# IR_Emitter.net
KiCad netlist of a schematic drawn in EAGLE
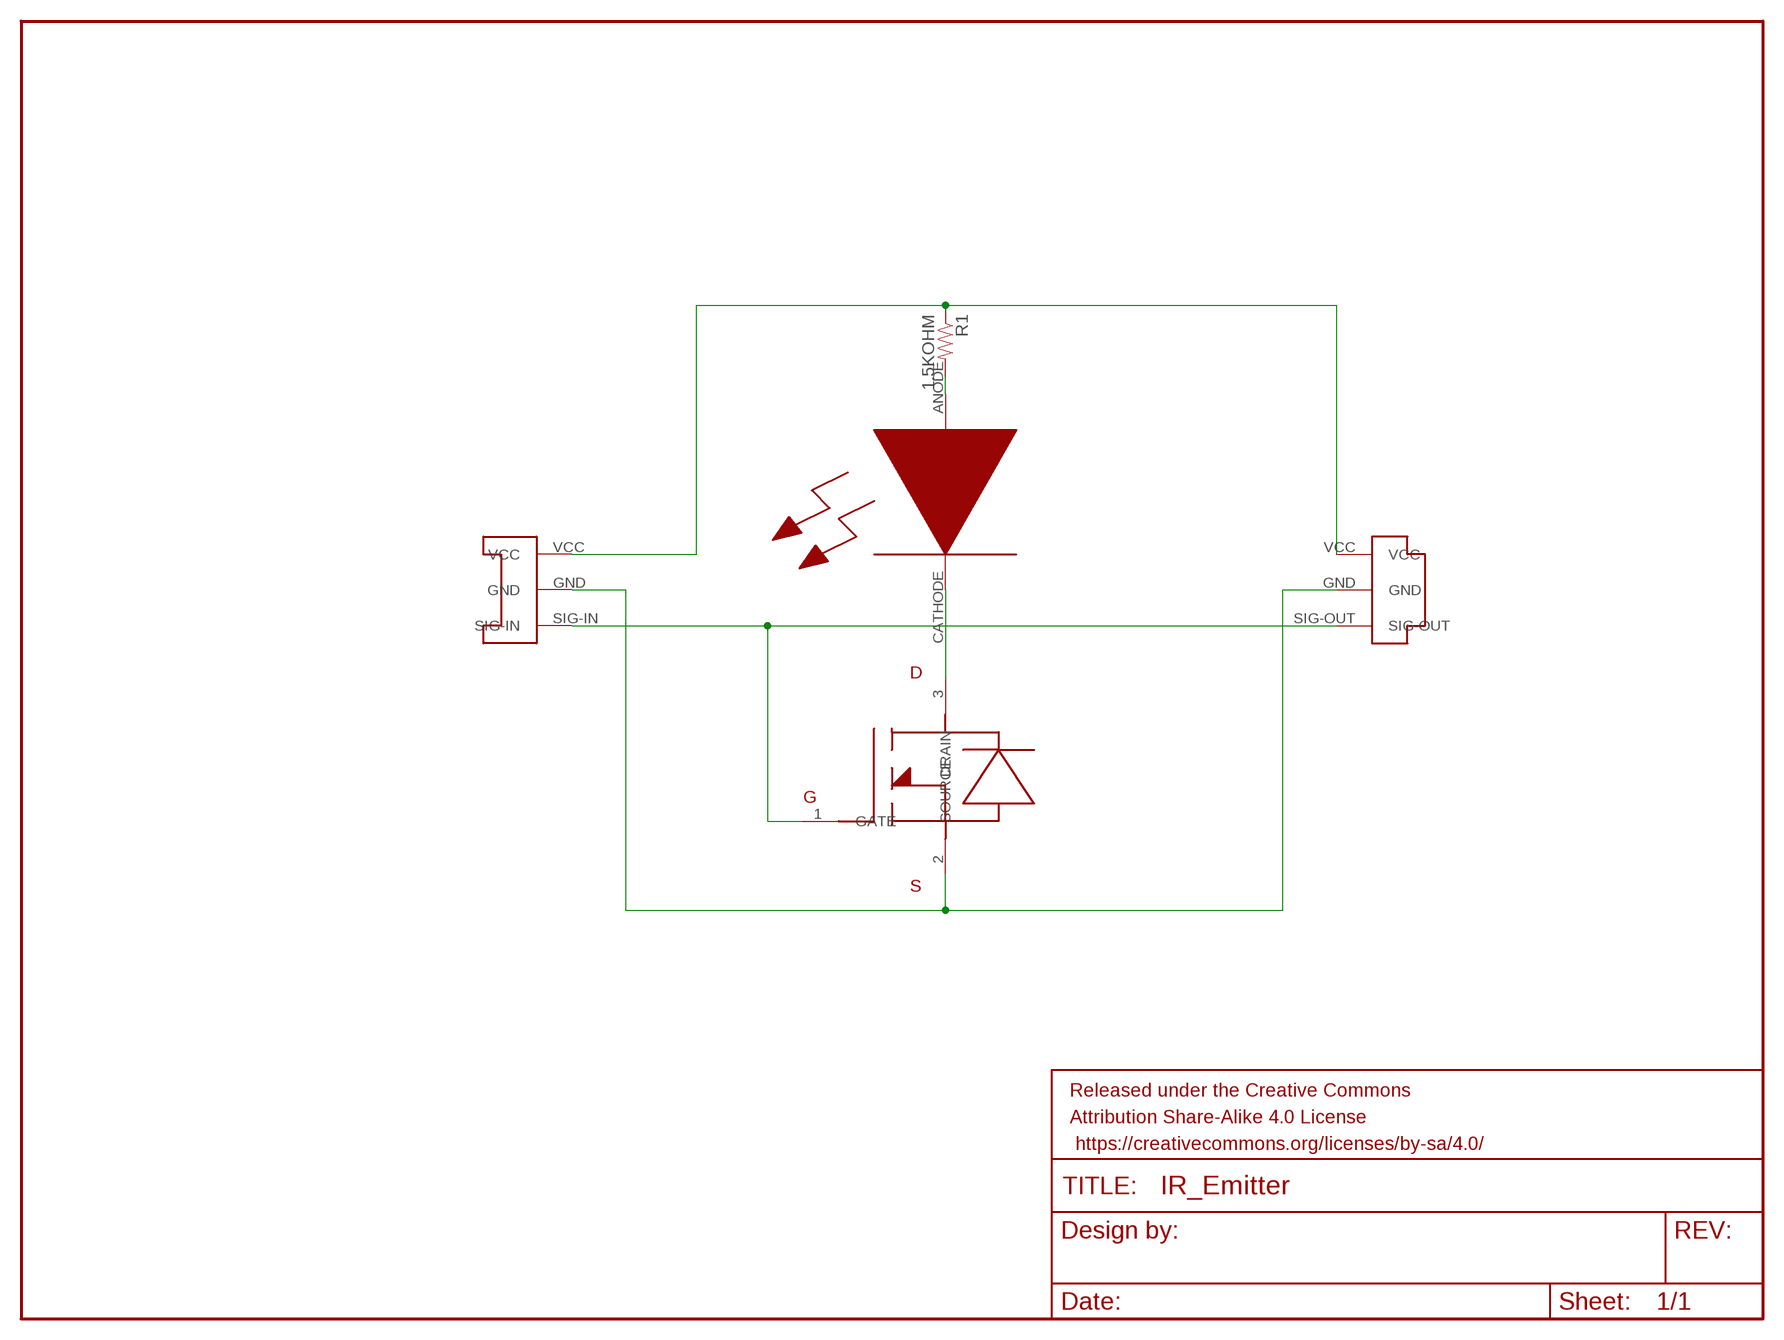
[diagram p0: schematic, sheet 1]

(export (version "E")
  (design (tool "Eeschema 10.0.6"))
  (components
    (comp (ref "FRAME1")
      (value "FRAME-LETTERNO_PACKAGE")
      (footprint "eagle-import:DUMMY")
      (fields (field (name "DESIGNER") "Nobody"))
      (libsource (lib "eagle-import") (part "FRAME-LETTERNO_PACKAGE"))
    )
    (comp (ref "R1")
      (value "1.5KOHM")
      (footprint "eagle-import:0603")
      (libsource (lib "eagle-import") (part "1.5KOHM-1/10W-1%(0603)"))
    )
    (comp (ref "U$1")
      (value "CONN-PLUG-3POS-3MM")
      (footprint "eagle-import:PLUG-3POS-3MM-SMD")
      (libsource (lib "eagle-import") (part "CONN-PLUG-3POS-3MM"))
    )
    (comp (ref "U$2")
      (value "CONN-SOCKET-3POS-3MM")
      (footprint "eagle-import:SOCKET-3POS-3MM-SMD")
      (libsource (lib "eagle-import") (part "CONN-SOCKET-3POS-3MM"))
    )
    (comp (ref "U$3")
      (value "MOSFET-N-CHAN")
      (footprint "eagle-import:SOT23-3")
      (libsource (lib "eagle-import") (part "MOSFET-N-CHAN"))
    )
    (comp (ref "U$4")
      (value "IR-EMITTER-VSMB2943G")
      (footprint "eagle-import:VEMD2020X01")
      (libsource (lib "eagle-import") (part "IR-EMITTER-VSMB2943G"))
    )
  )
  (nets
    (net (code "1") (name "Net-(R1-Pad1)") (class "Default")
      (node (ref "R1") (pin "1") (pinfunction "1_1") (pintype "passive"))
      (node (ref "U$1") (pin "VCC") (pinfunction "VCC_VCC") (pintype "power_in"))
      (node (ref "U$2") (pin "VCC") (pinfunction "VCC_VCC") (pintype "power_in"))
    )
    (net (code "2") (name "Net-(R1-Pad2)") (class "Default")
      (node (ref "R1") (pin "2") (pinfunction "2_2") (pintype "passive"))
      (node (ref "U$4") (pin "ANODE") (pinfunction "ANODE_ANODE") (pintype "passive"))
    )
    (net (code "3") (name "Net-(U$3-DRAIN)") (class "Default")
      (node (ref "U$3") (pin "3") (pinfunction "DRAIN_3") (pintype "passive"))
      (node (ref "U$4") (pin "CATHODE") (pinfunction "CATHODE_CATHODE") (pintype "passive"))
    )
    (net (code "4") (name "Net-(U$3-GATE)") (class "Default")
      (node (ref "U$1") (pin "SIG-OUT") (pinfunction "SIG-OUT_SIG-OUT") (pintype "bidirectional"))
      (node (ref "U$2") (pin "SIG-IN") (pinfunction "SIG-IN_SIG-IN") (pintype "bidirectional"))
      (node (ref "U$3") (pin "1") (pinfunction "GATE_1") (pintype "input"))
    )
    (net (code "5") (name "Net-(U$3-SOURCE)") (class "Default")
      (node (ref "U$1") (pin "GND") (pinfunction "GND_GND") (pintype "power_in"))
      (node (ref "U$2") (pin "GND") (pinfunction "GND_GND") (pintype "power_in"))
      (node (ref "U$3") (pin "2") (pinfunction "SOURCE_2") (pintype "passive"))
    )
  )
)
